# sd-card.net
KiCad netlist of a schematic drawn in Altium Designer
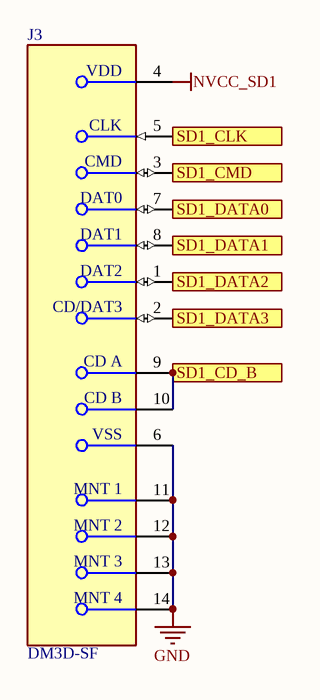
[diagram p0: sd-card.SchDoc]

(export (version "E")
  (design (tool "Eeschema 10.0.6"))
  (components
    (comp (ref "J3")
      (value "DM3D-SF")
      (footprint "FP-DM3D-SF-MFG")
      (description "CONN MICRO SD CARD PUSH-PULL")
      (libsource (lib "Altium Content Vault") (part "375756fe1061de806c40c19e9001ea3"))
    )
  )
  (nets
    (net (code "1") (name "/SD1_CD_B") (class "Default")
      (node (ref "J3") (pin "10") (pinfunction "CD_B_10") (pintype "passive"))
      (node (ref "J3") (pin "9") (pinfunction "CD_A_9") (pintype "passive"))
    )
    (net (code "2") (name "/SD1_CLK") (class "Default")
      (node (ref "J3") (pin "5") (pinfunction "CLK_5") (pintype "input"))
    )
    (net (code "3") (name "/SD1_CMD") (class "Default")
      (node (ref "J3") (pin "3") (pinfunction "CMD_3") (pintype "bidirectional"))
    )
    (net (code "4") (name "/SD1_DATA0") (class "Default")
      (node (ref "J3") (pin "7") (pinfunction "DAT0_7") (pintype "bidirectional"))
    )
    (net (code "5") (name "/SD1_DATA1") (class "Default")
      (node (ref "J3") (pin "8") (pinfunction "DAT1_8") (pintype "bidirectional"))
    )
    (net (code "6") (name "/SD1_DATA2") (class "Default")
      (node (ref "J3") (pin "1") (pinfunction "DAT2_1") (pintype "bidirectional"))
    )
    (net (code "7") (name "/SD1_DATA3") (class "Default")
      (node (ref "J3") (pin "2") (pinfunction "CD/DAT3_2") (pintype "bidirectional"))
    )
    (net (code "8") (name "GND") (class "Default")
      (node (ref "J3") (pin "11") (pinfunction "MNT_1_11") (pintype "passive"))
      (node (ref "J3") (pin "12") (pinfunction "MNT_2_12") (pintype "passive"))
      (node (ref "J3") (pin "13") (pinfunction "MNT_3_13") (pintype "passive"))
      (node (ref "J3") (pin "14") (pinfunction "MNT_4_14") (pintype "passive"))
      (node (ref "J3") (pin "6") (pinfunction "VSS_6") (pintype "power_in"))
    )
    (net (code "9") (name "NVCC_SD1") (class "Default")
      (node (ref "J3") (pin "4") (pinfunction "VDD_4") (pintype "power_in"))
    )
  )
)
